# design.net
KiCad netlist of a schematic drawn in Altium Designer
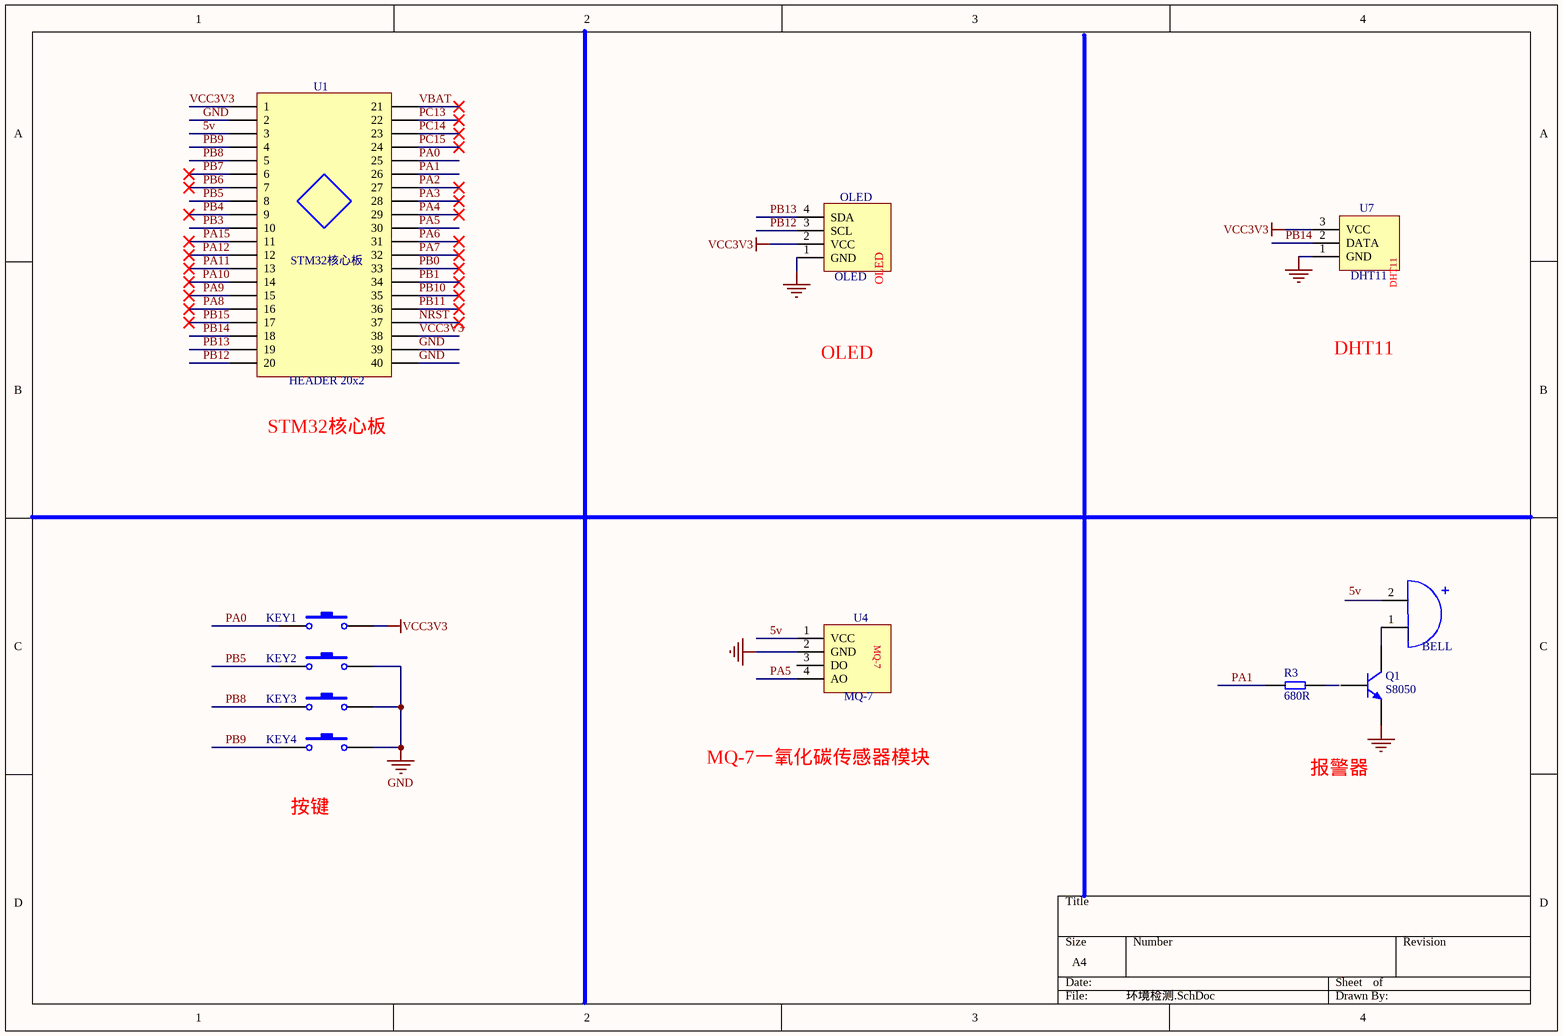
[diagram p0: 环境检测.SchDoc]

(export (version "E")
  (design (tool "Eeschema 10.0.6"))
  (components
    (comp (ref "BELL") (value "BELL") (footprint "BELL") (libsource (lib "wifi智能家居") (part "BELL")))
    (comp (ref "KEY1") (value "SW-PB") (footprint "SW-PB") (libsource (lib "wifi智能家居") (part "SW-PB")))
    (comp (ref "KEY2") (value "SW-PB") (footprint "SW-PB") (libsource (lib "wifi智能家居") (part "SW-PB")))
    (comp (ref "KEY3") (value "SW-PB") (footprint "SW-PB") (libsource (lib "wifi智能家居") (part "SW-PB")))
    (comp (ref "KEY4") (value "SW-PB") (footprint "SW-PB") (libsource (lib "wifi智能家居") (part "SW-PB")))
    (comp (ref "OLED") (value "OLED") (footprint "OLED") (libsource (lib "wifi智能家居") (part "OLED")))
    (comp (ref "Q1")
      (value "S8050")
      (footprint "TO-92A")
      (description "NPN General Purpose Amplifier")
      (fields (field (name "PUBLISHER") "Altium Limited"))
      (libsource (lib "Miscellaneous Devices") (part "2N3904"))
    )
    (comp (ref "R3") (value "680R") (footprint "RES") (libsource (lib "wifi智能家居") (part "RES")))
    (comp (ref "U1")
      (value "HEADER 20x2")
      (footprint "HEADER 20x2")
      (libsource (lib "wifi智能家居") (part "stm32核心板"))
    )
    (comp (ref "U4") (value "MQ-7") (footprint "MQ") (libsource (lib "wifi智能家居") (part "MQ-7")))
    (comp (ref "U7") (value "DHT11") (footprint "DHT11") (libsource (lib "wifi智能家居") (part "DHT11")))
  )
  (nets
    (net (code "1") (name "/5v") (class "Default")
      (node (ref "U1") (pin "3") (pinfunction "3_3") (pintype "passive"))
      (node (ref "U4") (pin "1") (pinfunction "VCC_1") (pintype "passive"))
    )
    (net (code "2") (name "/NRST") (class "Default")
      (node (ref "U1") (pin "37") (pinfunction "37_37") (pintype "passive+no_connect"))
    )
    (net (code "3") (name "/PA0") (class "Default")
      (node (ref "KEY1") (pin "1") (pinfunction "1_1") (pintype "passive"))
      (node (ref "U1") (pin "25") (pinfunction "25_25") (pintype "passive"))
    )
    (net (code "4") (name "/PA1") (class "Default")
      (node (ref "R3") (pin "1") (pinfunction "1_1") (pintype "passive"))
      (node (ref "U1") (pin "26") (pinfunction "26_26") (pintype "passive"))
    )
    (net (code "5") (name "/PA2") (class "Default")
      (node (ref "U1") (pin "27") (pinfunction "27_27") (pintype "passive+no_connect"))
    )
    (net (code "6") (name "/PA3") (class "Default")
      (node (ref "U1") (pin "28") (pinfunction "28_28") (pintype "passive+no_connect"))
    )
    (net (code "7") (name "/PA4") (class "Default")
      (node (ref "U1") (pin "29") (pinfunction "29_29") (pintype "passive+no_connect"))
    )
    (net (code "8") (name "/PA5") (class "Default")
      (node (ref "U1") (pin "30") (pinfunction "30_30") (pintype "passive"))
      (node (ref "U4") (pin "4") (pinfunction "AO_4") (pintype "passive"))
    )
    (net (code "9") (name "/PA6") (class "Default")
      (node (ref "U1") (pin "31") (pinfunction "31_31") (pintype "passive+no_connect"))
    )
    (net (code "10") (name "/PA7") (class "Default")
      (node (ref "U1") (pin "32") (pinfunction "32_32") (pintype "passive+no_connect"))
    )
    (net (code "11") (name "/PA8") (class "Default")
      (node (ref "U1") (pin "16") (pinfunction "16_16") (pintype "passive+no_connect"))
    )
    (net (code "12") (name "/PA9") (class "Default")
      (node (ref "U1") (pin "15") (pinfunction "15_15") (pintype "passive+no_connect"))
    )
    (net (code "13") (name "/PA10") (class "Default")
      (node (ref "U1") (pin "14") (pinfunction "14_14") (pintype "passive+no_connect"))
    )
    (net (code "14") (name "/PA11") (class "Default")
      (node (ref "U1") (pin "13") (pinfunction "13_13") (pintype "passive+no_connect"))
    )
    (net (code "15") (name "/PA12") (class "Default")
      (node (ref "U1") (pin "12") (pinfunction "12_12") (pintype "passive+no_connect"))
    )
    (net (code "16") (name "/PA15") (class "Default")
      (node (ref "U1") (pin "11") (pinfunction "11_11") (pintype "passive+no_connect"))
    )
    (net (code "17") (name "/PB0") (class "Default")
      (node (ref "U1") (pin "33") (pinfunction "33_33") (pintype "passive+no_connect"))
    )
    (net (code "18") (name "/PB1") (class "Default")
      (node (ref "U1") (pin "34") (pinfunction "34_34") (pintype "passive+no_connect"))
    )
    (net (code "19") (name "/PB3") (class "Default")
      (node (ref "U1") (pin "10") (pinfunction "10_10") (pintype "passive"))
    )
    (net (code "20") (name "/PB4") (class "Default")
      (node (ref "U1") (pin "9") (pinfunction "9_9") (pintype "passive+no_connect"))
    )
    (net (code "21") (name "/PB5") (class "Default")
      (node (ref "KEY2") (pin "1") (pinfunction "1_1") (pintype "passive"))
      (node (ref "U1") (pin "8") (pinfunction "8_8") (pintype "passive"))
    )
    (net (code "22") (name "/PB6") (class "Default")
      (node (ref "U1") (pin "7") (pinfunction "7_7") (pintype "passive+no_connect"))
    )
    (net (code "23") (name "/PB7") (class "Default")
      (node (ref "U1") (pin "6") (pinfunction "6_6") (pintype "passive+no_connect"))
    )
    (net (code "24") (name "/PB8") (class "Default")
      (node (ref "KEY3") (pin "1") (pinfunction "1_1") (pintype "passive"))
      (node (ref "U1") (pin "5") (pinfunction "5_5") (pintype "passive"))
    )
    (net (code "25") (name "/PB9") (class "Default")
      (node (ref "KEY4") (pin "1") (pinfunction "1_1") (pintype "passive"))
      (node (ref "U1") (pin "4") (pinfunction "4_4") (pintype "passive"))
    )
    (net (code "26") (name "/PB10") (class "Default")
      (node (ref "U1") (pin "35") (pinfunction "35_35") (pintype "passive+no_connect"))
    )
    (net (code "27") (name "/PB11") (class "Default")
      (node (ref "U1") (pin "36") (pinfunction "36_36") (pintype "passive+no_connect"))
    )
    (net (code "28") (name "/PB12") (class "Default")
      (node (ref "OLED") (pin "3") (pinfunction "SCL_3") (pintype "passive"))
      (node (ref "U1") (pin "20") (pinfunction "20_20") (pintype "passive"))
    )
    (net (code "29") (name "/PB13") (class "Default")
      (node (ref "OLED") (pin "4") (pinfunction "SDA_4") (pintype "passive"))
      (node (ref "U1") (pin "19") (pinfunction "19_19") (pintype "passive"))
    )
    (net (code "30") (name "/PB14") (class "Default")
      (node (ref "U1") (pin "18") (pinfunction "18_18") (pintype "passive"))
      (node (ref "U7") (pin "2") (pinfunction "DATA_2") (pintype "passive"))
    )
    (net (code "31") (name "/PB15") (class "Default")
      (node (ref "U1") (pin "17") (pinfunction "17_17") (pintype "passive+no_connect"))
    )
    (net (code "32") (name "/PC13") (class "Default")
      (node (ref "U1") (pin "22") (pinfunction "22_22") (pintype "passive+no_connect"))
    )
    (net (code "33") (name "/PC14") (class "Default")
      (node (ref "U1") (pin "23") (pinfunction "23_23") (pintype "passive+no_connect"))
    )
    (net (code "34") (name "/PC15") (class "Default")
      (node (ref "U1") (pin "24") (pinfunction "24_24") (pintype "passive+no_connect"))
    )
    (net (code "35") (name "/VBAT") (class "Default")
      (node (ref "U1") (pin "21") (pinfunction "21_21") (pintype "passive+no_connect"))
    )
    (net (code "36") (name "GND") (class "Default")
      (node (ref "KEY2") (pin "2") (pinfunction "2_2") (pintype "passive"))
      (node (ref "KEY3") (pin "2") (pinfunction "2_2") (pintype "passive"))
      (node (ref "KEY4") (pin "2") (pinfunction "2_2") (pintype "passive"))
      (node (ref "OLED") (pin "1") (pinfunction "GND_1") (pintype "passive"))
      (node (ref "Q1") (pin "1") (pinfunction "E_1") (pintype "passive"))
      (node (ref "U1") (pin "2") (pinfunction "2_2") (pintype "passive"))
      (node (ref "U1") (pin "39") (pinfunction "39_39") (pintype "passive"))
      (node (ref "U1") (pin "40") (pinfunction "40_40") (pintype "passive"))
      (node (ref "U4") (pin "2") (pinfunction "GND_2") (pintype "passive"))
      (node (ref "U7") (pin "1") (pinfunction "GND_1") (pintype "passive"))
    )
    (net (code "37") (name "Net-(Q1-C)") (class "Default")
      (node (ref "BELL") (pin "1") (pinfunction "1_1") (pintype "passive"))
      (node (ref "Q1") (pin "3") (pinfunction "C_3") (pintype "passive"))
    )
    (net (code "38") (name "VCC3V3") (class "Default")
      (node (ref "KEY1") (pin "2") (pinfunction "2_2") (pintype "passive"))
      (node (ref "OLED") (pin "2") (pinfunction "VCC_2") (pintype "passive"))
      (node (ref "U1") (pin "1") (pinfunction "1_1") (pintype "passive"))
      (node (ref "U1") (pin "38") (pinfunction "38_38") (pintype "passive"))
      (node (ref "U7") (pin "3") (pinfunction "VCC_3") (pintype "passive"))
    )
    (net (code "39") (name "unconnected-(BELL-Pad2)") (class "Default")
      (node (ref "BELL") (pin "2") (pinfunction "2_2") (pintype "passive"))
    )
    (net (code "40") (name "unconnected-(Q1-B-Pad2)") (class "Default")
      (node (ref "Q1") (pin "2") (pinfunction "B_2") (pintype "passive"))
    )
    (net (code "41") (name "unconnected-(R3-Pad2)") (class "Default")
      (node (ref "R3") (pin "2") (pinfunction "2_2") (pintype "passive"))
    )
    (net (code "42") (name "unconnected-(U4-DO-Pad3)") (class "Default")
      (node (ref "U4") (pin "3") (pinfunction "DO_3") (pintype "passive"))
    )
  )
)
